# Sheet1.net
KiCad netlist of a schematic drawn in Altium Designer
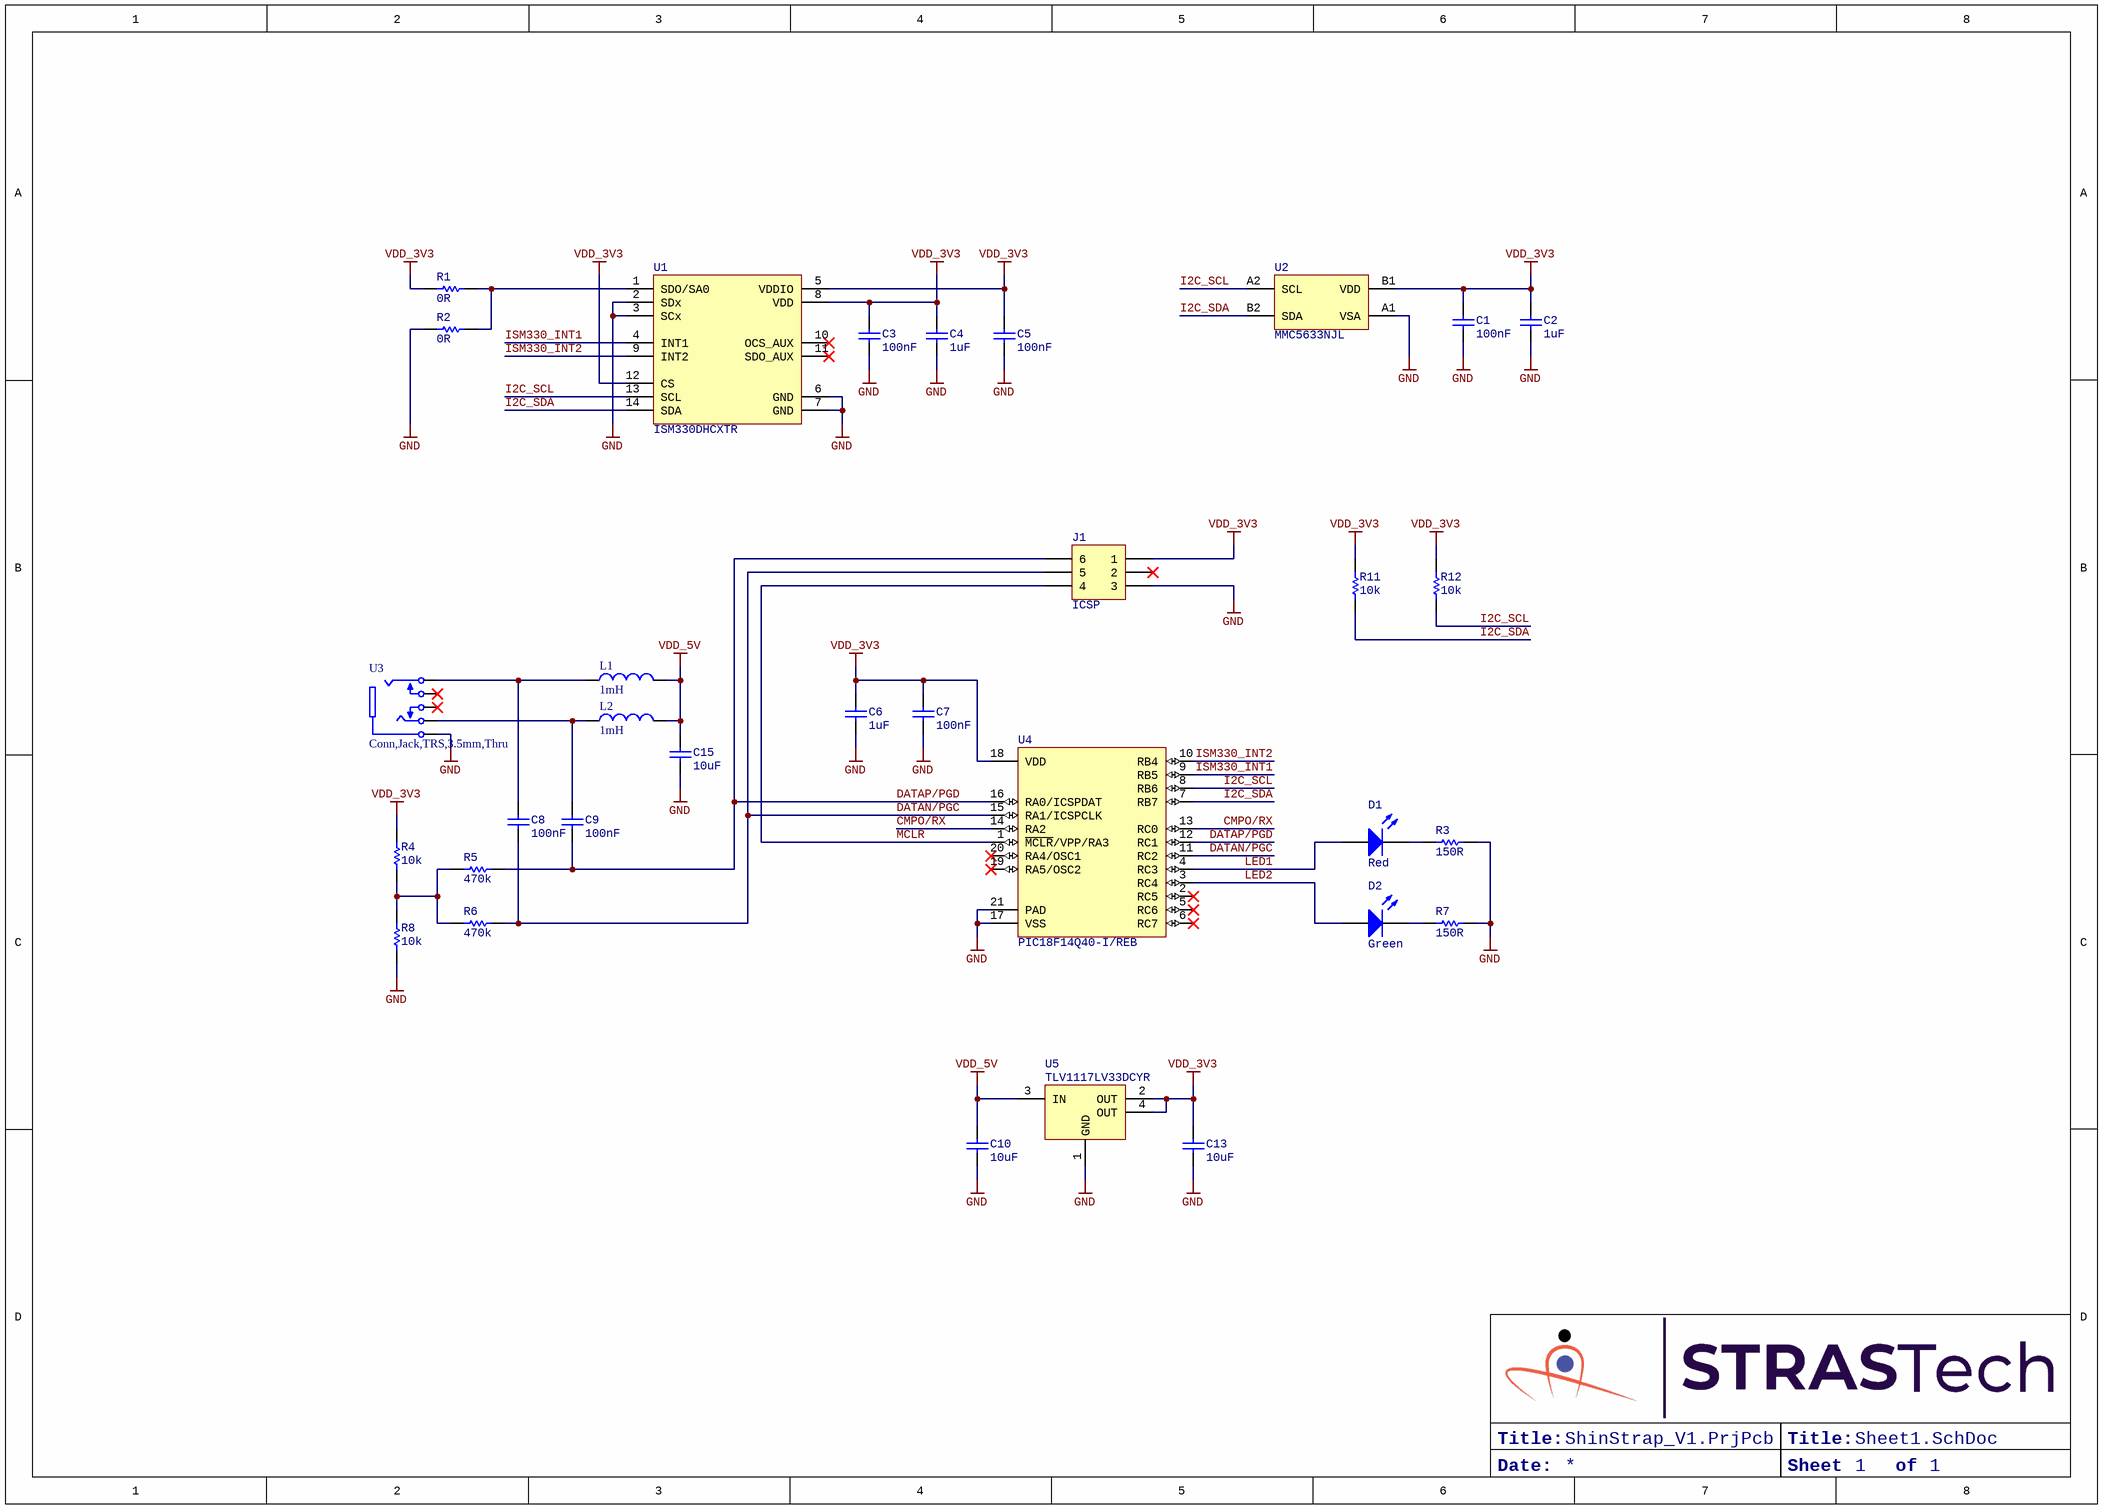
[diagram p0: Sheet1.SchDoc]

(export (version "E")
  (design (tool "Eeschema 10.0.6"))
  (components
    (comp (ref "C1")
      (value "100nF")
      (footprint "Cap,SMD,0402")
      (description "0.1µF ±10% 25V Ceramic Capacitor X7R 0402 (1005 Metric)")
      (fields
        (field (name "VENDOR PART NUMBER") "490-14603-1-ND")
        (field (name "MANUFACTURER") "Murata Electronics")
        (field (name "CREATEDBY") "Judd Foster")
      )
      (libsource (lib "symbols") (part "CAP,Cer,100nF,25VDC,X7R,0402"))
    )
    (comp (ref "C2")
      (value "1uF")
      (footprint "Cap,SMD,0402")
      (description "1 µF ±10% 35V Ceramic Capacitor X5R 0402 (1005 Metric)")
      (fields
        (field (name "VENDOR PART NUMBER") "445-9073-1-ND")
        (field (name "MANUFACTURER") "TDK Corporation")
        (field (name "CREATEDBY") "Judd Foster")
      )
      (libsource (lib "symbols") (part "CAP,Cer,1uF,35VDC,X5R,0402"))
    )
    (comp (ref "C3")
      (value "100nF")
      (footprint "Cap,SMD,0402")
      (description "0.1µF ±10% 25V Ceramic Capacitor X7R 0402 (1005 Metric)")
      (fields
        (field (name "VENDOR PART NUMBER") "490-14603-1-ND")
        (field (name "MANUFACTURER") "Murata Electronics")
        (field (name "CREATEDBY") "Judd Foster")
      )
      (libsource (lib "symbols") (part "CAP,Cer,100nF,25VDC,X7R,0402"))
    )
    (comp (ref "C4")
      (value "1uF")
      (footprint "Cap,SMD,0402")
      (description "1 µF ±10% 35V Ceramic Capacitor X5R 0402 (1005 Metric)")
      (fields
        (field (name "VENDOR PART NUMBER") "445-9073-1-ND")
        (field (name "MANUFACTURER") "TDK Corporation")
        (field (name "CREATEDBY") "Judd Foster")
      )
      (libsource (lib "symbols") (part "CAP,Cer,1uF,35VDC,X5R,0402"))
    )
    (comp (ref "C5")
      (value "100nF")
      (footprint "Cap,SMD,0402")
      (description "0.1µF ±10% 25V Ceramic Capacitor X7R 0402 (1005 Metric)")
      (fields
        (field (name "VENDOR PART NUMBER") "490-14603-1-ND")
        (field (name "MANUFACTURER") "Murata Electronics")
        (field (name "CREATEDBY") "Judd Foster")
      )
      (libsource (lib "symbols") (part "CAP,Cer,100nF,25VDC,X7R,0402"))
    )
    (comp (ref "C6")
      (value "1uF")
      (footprint "Cap,SMD,0402")
      (description "1 µF ±10% 35V Ceramic Capacitor X5R 0402 (1005 Metric)")
      (fields
        (field (name "VENDOR PART NUMBER") "445-9073-1-ND")
        (field (name "MANUFACTURER") "TDK Corporation")
        (field (name "CREATEDBY") "Judd Foster")
      )
      (libsource (lib "symbols") (part "CAP,Cer,1uF,35VDC,X5R,0402"))
    )
    (comp (ref "C7")
      (value "100nF")
      (footprint "Cap,SMD,0402")
      (description "0.1µF ±10% 25V Ceramic Capacitor X7R 0402 (1005 Metric)")
      (fields
        (field (name "VENDOR PART NUMBER") "490-14603-1-ND")
        (field (name "MANUFACTURER") "Murata Electronics")
        (field (name "CREATEDBY") "Judd Foster")
      )
      (libsource (lib "symbols") (part "CAP,Cer,100nF,25VDC,X7R,0402"))
    )
    (comp (ref "C8")
      (value "100nF")
      (footprint "Cap,SMD,0402")
      (description "0.1µF ±10% 25V Ceramic Capacitor X7R 0402 (1005 Metric)")
      (fields
        (field (name "VENDOR PART NUMBER") "490-14603-1-ND")
        (field (name "MANUFACTURER") "Murata Electronics")
        (field (name "CREATEDBY") "Judd Foster")
      )
      (libsource (lib "symbols") (part "CAP,Cer,100nF,25VDC,X7R,0402"))
    )
    (comp (ref "C9")
      (value "100nF")
      (footprint "Cap,SMD,0402")
      (description "0.1µF ±10% 25V Ceramic Capacitor X7R 0402 (1005 Metric)")
      (fields
        (field (name "VENDOR PART NUMBER") "490-14603-1-ND")
        (field (name "MANUFACTURER") "Murata Electronics")
        (field (name "CREATEDBY") "Judd Foster")
      )
      (libsource (lib "symbols") (part "CAP,Cer,100nF,25VDC,X7R,0402"))
    )
    (comp (ref "C10")
      (value "10uF")
      (footprint "Cap,SMD,0402")
      (description "10 µF ±20% 10V Ceramic Capacitor X5R 0402 (1005 Metric)")
      (fields
        (field (name "VENDOR PART NUMBER") "1276-1450-1-ND")
        (field (name "MANUFACTURER") "Samsung Electro-Mechanics")
        (field (name "CREATEDBY") "Judd Foster")
      )
      (libsource (lib "symbols") (part "CAP,Cer,10uF,10VDC,X5R,0402"))
    )
    (comp (ref "C13")
      (value "10uF")
      (footprint "Cap,SMD,0402")
      (description "10 µF ±20% 10V Ceramic Capacitor X5R 0402 (1005 Metric)")
      (fields
        (field (name "VENDOR PART NUMBER") "1276-1450-1-ND")
        (field (name "MANUFACTURER") "Samsung Electro-Mechanics")
        (field (name "CREATEDBY") "Judd Foster")
      )
      (libsource (lib "symbols") (part "CAP,Cer,10uF,10VDC,X5R,0402"))
    )
    (comp (ref "C15")
      (value "10uF")
      (footprint "Cap,SMD,0402")
      (description "10 µF ±20% 10V Ceramic Capacitor X5R 0402 (1005 Metric)")
      (fields
        (field (name "VENDOR PART NUMBER") "1276-1450-1-ND")
        (field (name "MANUFACTURER") "Samsung Electro-Mechanics")
        (field (name "CREATEDBY") "Judd Foster")
      )
      (libsource (lib "symbols") (part "CAP,Cer,10uF,10VDC,X5R,0402"))
    )
    (comp (ref "D1")
      (value "Red")
      (footprint "LED,0603")
      (description "Red 633nm LED Indication - Discrete 2V 0603 (1608 Metric)")
      (fields
        (field (name "MANUFACTURER") "Lite-On Inc.")
        (field (name "MANUFACTURER PART NUMBER") "LS Q976-NR-1")
        (field (name "CREATEDBY") "Judd Foster")
      )
      (libsource (lib "symbols") (part "LED,Red,SMD,0603"))
    )
    (comp (ref "D2")
      (value "Green")
      (footprint "LED,0603")
      (description "Green 530nm LED Indication - Discrete 3V 0603 (1608 Metric)")
      (fields
        (field (name "MANUFACTURER") "Stanley Electric Co")
        (field (name "MANUFACTURER PART NUMBER") "THG1111C-0005-TR")
        (field (name "CREATEDBY") "Judd Foster")
      )
      (libsource (lib "symbols") (part "LED,Green,SMD,0603"))
    )
    (comp (ref "J1")
      (value "Term,Header,3x2 Pin,1.27mm,SMD")
      (footprint "TERM,HEADER,3X2PIN,P1.27,SMD")
      (description "Connector Header Surface Mount 6 position 0.050\" (1.27mm)")
      (fields
        (field (name "VENDOR PART NUMBER") "609-3693-1-ND")
        (field (name "MANUFACTURER") "Amphenol ICC (FCI)")
        (field (name "CREATEDBY") "Judd Foster")
      )
      (libsource (lib "symbols") (part "Term,Header,3x2 Pin,1.27mm,SMD"))
    )
    (comp (ref "L1")
      (value "1mH")
      (footprint "IND,1210")
      (description "1 mH Unshielded Wirewound Inductor 100 mA 16.9Ohm Max 1210 (3225 Metric)")
      (fields
        (field (name "VENDOR PART NUMBER") "587-CBC3225T102MRCT-ND")
        (field (name "MANUFACTURER") "Taiyo Yuden")
        (field (name "CREATEDBY") "Judd Foster")
      )
      (libsource (lib "symbols") (part "IND,1mH,100mA,Wirewound,1210"))
    )
    (comp (ref "L2")
      (value "1mH")
      (footprint "IND,1210")
      (description "1 mH Unshielded Wirewound Inductor 100 mA 16.9Ohm Max 1210 (3225 Metric)")
      (fields
        (field (name "VENDOR PART NUMBER") "587-CBC3225T102MRCT-ND")
        (field (name "MANUFACTURER") "Taiyo Yuden")
        (field (name "CREATEDBY") "Judd Foster")
      )
      (libsource (lib "symbols") (part "IND,1mH,100mA,Wirewound,1210"))
    )
    (comp (ref "R1")
      (value "0R")
      (footprint "RES,0402")
      (description "0 Ohms Jumper 0.1W, 1/10W Chip Resistor 0402 (1005 Metric) Automotive AEC-Q200 Thick Film")
      (fields
        (field (name "MANUFACTURER") "Panasonic Electronic Components")
        (field (name "MANUFACTURER PART NUMBER") "ERJ-2GE0R00X")
        (field (name "CREATEDBY") "Judd Foster")
      )
      (libsource (lib "symbols") (part "RES,0R0,0.1W,0402"))
    )
    (comp (ref "R2")
      (value "0R")
      (footprint "RES,0402")
      (description "0 Ohms Jumper 0.1W, 1/10W Chip Resistor 0402 (1005 Metric) Automotive AEC-Q200 Thick Film")
      (fields
        (field (name "MANUFACTURER") "Panasonic Electronic Components")
        (field (name "MANUFACTURER PART NUMBER") "ERJ-2GE0R00X")
        (field (name "CREATEDBY") "Judd Foster")
      )
      (libsource (lib "symbols") (part "RES,0R0,0.1W,0402"))
    )
    (comp (ref "R3")
      (value "150R")
      (footprint "RES,0402")
      (fields
        (field (name "MANUFACTURER") "TE Connectivity Passive Product")
        (field (name "MANUFACTURER PART NUMBER") "CRGCQ0402F150R")
        (field (name "VENDOR PART NUMBER") "A129617CT-ND")
        (field (name "CREATEDBY") "Judd Foster")
      )
      (libsource (lib "symbols") (part "RES,150R,1%,0.1W,0402"))
    )
    (comp (ref "R4")
      (value "10k")
      (footprint "RES,0402")
      (description "10 kOhms ±5% 0.063W, 1/16W Chip Resistor 0402 (1005 Metric) Automotive AEC-Q200 Thick Film")
      (fields
        (field (name "VENDOR PART NUMBER") "RMCF0402JT10K0CT-ND")
        (field (name "MANUFACTURER") "Stackpole Electronics Inc")
        (field (name "CREATEDBY") "Judd Foster")
      )
      (libsource (lib "symbols") (part "RES,10k,5%,0.063W,0402"))
    )
    (comp (ref "R5")
      (value "470k")
      (footprint "RES,0402")
      (description "470 kOhms ±5% 0.063W, 1/16W Chip Resistor 0402 (1005 Metric) Automotive AEC-Q200 Thick Film")
      (fields
        (field (name "MANUFACTURER") "Stackpole Electronics Inc")
        (field (name "MANUFACTURER PART NUMBER") "RMCF0402JT470K")
        (field (name "CREATEDBY") "Judd Foster")
      )
      (libsource (lib "symbols") (part "RES,470k,5%,0.063W,0402"))
    )
    (comp (ref "R6")
      (value "470k")
      (footprint "RES,0402")
      (description "470 kOhms ±5% 0.063W, 1/16W Chip Resistor 0402 (1005 Metric) Automotive AEC-Q200 Thick Film")
      (fields
        (field (name "MANUFACTURER") "Stackpole Electronics Inc")
        (field (name "MANUFACTURER PART NUMBER") "RMCF0402JT470K")
        (field (name "CREATEDBY") "Judd Foster")
      )
      (libsource (lib "symbols") (part "RES,470k,5%,0.063W,0402"))
    )
    (comp (ref "R7")
      (value "150R")
      (footprint "RES,0402")
      (fields
        (field (name "MANUFACTURER") "TE Connectivity Passive Product")
        (field (name "MANUFACTURER PART NUMBER") "CRGCQ0402F150R")
        (field (name "VENDOR PART NUMBER") "A129617CT-ND")
        (field (name "CREATEDBY") "Judd Foster")
      )
      (libsource (lib "symbols") (part "RES,150R,1%,0.1W,0402"))
    )
    (comp (ref "R8")
      (value "10k")
      (footprint "RES,0402")
      (description "10 kOhms ±5% 0.063W, 1/16W Chip Resistor 0402 (1005 Metric) Automotive AEC-Q200 Thick Film")
      (fields
        (field (name "VENDOR PART NUMBER") "RMCF0402JT10K0CT-ND")
        (field (name "MANUFACTURER") "Stackpole Electronics Inc")
        (field (name "CREATEDBY") "Judd Foster")
      )
      (libsource (lib "symbols") (part "RES,10k,5%,0.063W,0402"))
    )
    (comp (ref "R11")
      (value "10k")
      (footprint "RES,0402")
      (description "10 kOhms ±5% 0.063W, 1/16W Chip Resistor 0402 (1005 Metric) Automotive AEC-Q200 Thick Film")
      (fields
        (field (name "VENDOR PART NUMBER") "RMCF0402JT10K0CT-ND")
        (field (name "MANUFACTURER") "Stackpole Electronics Inc")
        (field (name "CREATEDBY") "Judd Foster")
      )
      (libsource (lib "symbols") (part "RES,10k,5%,0.063W,0402"))
    )
    (comp (ref "R12")
      (value "10k")
      (footprint "RES,0402")
      (description "10 kOhms ±5% 0.063W, 1/16W Chip Resistor 0402 (1005 Metric) Automotive AEC-Q200 Thick Film")
      (fields
        (field (name "VENDOR PART NUMBER") "RMCF0402JT10K0CT-ND")
        (field (name "MANUFACTURER") "Stackpole Electronics Inc")
        (field (name "CREATEDBY") "Judd Foster")
      )
      (libsource (lib "symbols") (part "RES,10k,5%,0.063W,0402"))
    )
    (comp (ref "U1")
      (value "ISM330DHCXTR")
      (footprint "IC,LGA-14L,2.5x3mm")
      (description "Accelerometer, Gyroscope, Temperature, 6 Axis Sensor I²C, SPI Output")
      (fields
        (field (name "MANUFACTURER") "STMicroelectronics")
        (field (name "VENDOR PART NUMBER") "497-19784-1-ND")
        (field (name "CREATEDBY") "Judd Foster")
      )
      (libsource (lib "symbols") (part "ISM330DHCXTR"))
    )
    (comp (ref "U2")
      (value "MMC5633NJL")
      (footprint "IC,WLP,2x2,P0.4mm")
      (description "Magnetoresistive Sensor X, Y, Z Axis 4-WLP (0.85x0.85)")
      (fields
        (field (name "MANUFACTURER") "Memsic Inc.")
        (field (name "VENDOR PART NUMBER") "1267-MMC5633NJLCT-ND")
        (field (name "CREATEDBY") "Judd Foster")
      )
      (libsource (lib "symbols") (part "MMC5633NJL"))
    )
    (comp (ref "U3")
      (value "Conn,Jack,TRS,3.5mm,Thru")
      (footprint "CONN,JACK,TRS,3.5MM,THRU")
      (fields
        (field (name "MANUFACTURER") "CUI Devices")
        (field (name "MANUFACTURER PART NUMBER") "SJ1-3525N")
        (field (name "VENDOR PART NUMBER") "CP1-3525N-ND")
        (field (name "CREATEDBY") "Judd Foster")
      )
      (libsource (lib "symbols") (part "Conn,Jack,TRS,3.5mm,Thru"))
    )
    (comp (ref "U4")
      (value "PIC18F14Q40-I/REB")
      (footprint "IC,QFN-20,3x3,PAD,P0.4")
      (description "PIC series Microcontroller IC 8-Bit 64MHz 16KB (16K x 8) FLASH 20-VQFN (3x3)")
      (fields
        (field (name "MANUFACTURER") "Microchip Technology")
        (field (name "VENDOR PART NUMBER") "150-PIC18F14Q40-I/REB-ND")
        (field (name "CREATEDBY") "Judd Foster")
      )
      (libsource (lib "symbols") (part "PIC18F14Q40-I/REB"))
    )
    (comp (ref "U5")
      (value "TLV1117LV33DCYR")
      (footprint "SOT223")
      (description "Linear Voltage Regulator IC  1 Output  1A SOT-223-4")
      (fields
        (field (name "MANUFACTURER") "Texas Instruments")
        (field (name "VENDOR PART NUMBER") "296-28778-1-ND")
        (field (name "CREATEDBY") "Judd Foster")
      )
      (libsource (lib "symbols") (part "TLV1117LV33DCYR"))
    )
  )
  (nets
    (net (code "1") (name "/CMPO{slash}RX") (class "Default")
      (node (ref "U4") (pin "13") (pinfunction "RC0_13") (pintype "bidirectional"))
      (node (ref "U4") (pin "14") (pinfunction "RA2_14") (pintype "bidirectional"))
    )
    (net (code "2") (name "/DATAN{slash}PGC") (class "Default")
      (node (ref "C8") (pin "1") (pinfunction "1_1") (pintype "passive"))
      (node (ref "J1") (pin "5") (pinfunction "5_5") (pintype "passive"))
      (node (ref "R6") (pin "1") (pinfunction "1_1") (pintype "passive"))
      (node (ref "U4") (pin "11") (pinfunction "RC2_11") (pintype "bidirectional"))
      (node (ref "U4") (pin "15") (pinfunction "RA1/ICSPCLK_15") (pintype "bidirectional"))
    )
    (net (code "3") (name "/DATAP{slash}PGD") (class "Default")
      (node (ref "C9") (pin "1") (pinfunction "1_1") (pintype "passive"))
      (node (ref "J1") (pin "6") (pinfunction "6_6") (pintype "passive"))
      (node (ref "R5") (pin "1") (pinfunction "1_1") (pintype "passive"))
      (node (ref "U4") (pin "12") (pinfunction "RC1_12") (pintype "bidirectional"))
      (node (ref "U4") (pin "16") (pinfunction "RA0/ICSPDAT_16") (pintype "bidirectional"))
    )
    (net (code "4") (name "/I2C_SCL") (class "Default")
      (node (ref "R12") (pin "1") (pinfunction "1_1") (pintype "passive"))
      (node (ref "U1") (pin "13") (pinfunction "SCL_13") (pintype "passive"))
      (node (ref "U2") (pin "A2") (pinfunction "SCL_A2") (pintype "passive"))
      (node (ref "U4") (pin "8") (pinfunction "RB6_8") (pintype "bidirectional"))
    )
    (net (code "5") (name "/I2C_SDA") (class "Default")
      (node (ref "R11") (pin "1") (pinfunction "1_1") (pintype "passive"))
      (node (ref "U1") (pin "14") (pinfunction "SDA_14") (pintype "passive"))
      (node (ref "U2") (pin "B2") (pinfunction "SDA_B2") (pintype "passive"))
      (node (ref "U4") (pin "7") (pinfunction "RB7_7") (pintype "bidirectional"))
    )
    (net (code "6") (name "/ISM330_INT1") (class "Default")
      (node (ref "U1") (pin "4") (pinfunction "INT1_4") (pintype "passive"))
      (node (ref "U4") (pin "9") (pinfunction "RB5_9") (pintype "bidirectional"))
    )
    (net (code "7") (name "/ISM330_INT2") (class "Default")
      (node (ref "U1") (pin "9") (pinfunction "INT2_9") (pintype "passive"))
      (node (ref "U4") (pin "10") (pinfunction "RB4_10") (pintype "bidirectional"))
    )
    (net (code "8") (name "/LED1") (class "Default")
      (node (ref "D1") (pin "1") (pinfunction "A_1") (pintype "passive"))
      (node (ref "U4") (pin "4") (pinfunction "RC3_4") (pintype "bidirectional"))
    )
    (net (code "9") (name "/LED2") (class "Default")
      (node (ref "D2") (pin "1") (pinfunction "A_1") (pintype "passive"))
      (node (ref "U4") (pin "3") (pinfunction "RC4_3") (pintype "bidirectional"))
    )
    (net (code "10") (name "/~{MCLR}") (class "Default")
      (node (ref "J1") (pin "4") (pinfunction "4_4") (pintype "passive"))
      (node (ref "U4") (pin "1") (pinfunction "~{MCLR}/VPP/RA3_1") (pintype "bidirectional"))
    )
    (net (code "11") (name "GND") (class "Default")
      (node (ref "C1") (pin "2") (pinfunction "2_2") (pintype "passive"))
      (node (ref "C10") (pin "1") (pinfunction "1_1") (pintype "passive"))
      (node (ref "C13") (pin "1") (pinfunction "1_1") (pintype "passive"))
      (node (ref "C15") (pin "1") (pinfunction "1_1") (pintype "passive"))
      (node (ref "C2") (pin "1") (pinfunction "1_1") (pintype "passive"))
      (node (ref "C3") (pin "1") (pinfunction "1_1") (pintype "passive"))
      (node (ref "C4") (pin "1") (pinfunction "1_1") (pintype "passive"))
      (node (ref "C5") (pin "1") (pinfunction "1_1") (pintype "passive"))
      (node (ref "C6") (pin "1") (pinfunction "1_1") (pintype "passive"))
      (node (ref "C7") (pin "1") (pinfunction "1_1") (pintype "passive"))
      (node (ref "J1") (pin "3") (pinfunction "3_3") (pintype "passive"))
      (node (ref "R2") (pin "1") (pinfunction "1_1") (pintype "passive"))
      (node (ref "R3") (pin "2") (pinfunction "2_2") (pintype "passive"))
      (node (ref "R7") (pin "2") (pinfunction "2_2") (pintype "passive"))
      (node (ref "R8") (pin "1") (pinfunction "1_1") (pintype "passive"))
      (node (ref "U1") (pin "2") (pinfunction "SDx_2") (pintype "passive"))
      (node (ref "U1") (pin "3") (pinfunction "SCx_3") (pintype "passive"))
      (node (ref "U1") (pin "6") (pinfunction "GND_6") (pintype "passive"))
      (node (ref "U1") (pin "7") (pinfunction "GND_7") (pintype "passive"))
      (node (ref "U2") (pin "A1") (pinfunction "VSA_A1") (pintype "passive"))
      (node (ref "U3") (pin "1") (pinfunction "S_1") (pintype "power_in"))
      (node (ref "U4") (pin "17") (pinfunction "VSS_17") (pintype "power_in"))
      (node (ref "U4") (pin "21") (pinfunction "PAD_21") (pintype "passive"))
      (node (ref "U5") (pin "1") (pinfunction "GND_1") (pintype "passive"))
    )
    (net (code "12") (name "Net-(D1-K)") (class "Default")
      (node (ref "D1") (pin "2") (pinfunction "K_2") (pintype "passive"))
      (node (ref "R3") (pin "1") (pinfunction "1_1") (pintype "passive"))
    )
    (net (code "13") (name "Net-(D2-K)") (class "Default")
      (node (ref "D2") (pin "2") (pinfunction "K_2") (pintype "passive"))
      (node (ref "R7") (pin "1") (pinfunction "1_1") (pintype "passive"))
    )
    (net (code "14") (name "Net-(R4-Pad1)") (class "Default")
      (node (ref "R4") (pin "1") (pinfunction "1_1") (pintype "passive"))
      (node (ref "R5") (pin "2") (pinfunction "2_2") (pintype "passive"))
      (node (ref "R6") (pin "2") (pinfunction "2_2") (pintype "passive"))
      (node (ref "R8") (pin "2") (pinfunction "2_2") (pintype "passive"))
    )
    (net (code "15") (name "Net-(U1-SDO{slash}SA0)") (class "Default")
      (node (ref "R1") (pin "2") (pinfunction "2_2") (pintype "passive"))
      (node (ref "R2") (pin "2") (pinfunction "2_2") (pintype "passive"))
      (node (ref "U1") (pin "1") (pinfunction "SDO/SA0_1") (pintype "passive"))
    )
    (net (code "16") (name "Net-(U3-R)") (class "Default")
      (node (ref "C8") (pin "2") (pinfunction "2_2") (pintype "passive"))
      (node (ref "L1") (pin "1") (pinfunction "1_1") (pintype "passive"))
      (node (ref "U3") (pin "3") (pinfunction "R_3") (pintype "passive"))
    )
    (net (code "17") (name "Net-(U3-T)") (class "Default")
      (node (ref "C9") (pin "2") (pinfunction "2_2") (pintype "passive"))
      (node (ref "L2") (pin "1") (pinfunction "1_1") (pintype "passive"))
      (node (ref "U3") (pin "2") (pinfunction "T_2") (pintype "passive"))
    )
    (net (code "18") (name "VDD_3V3") (class "Default")
      (node (ref "C1") (pin "1") (pinfunction "1_1") (pintype "passive"))
      (node (ref "C13") (pin "2") (pinfunction "2_2") (pintype "passive"))
      (node (ref "C2") (pin "2") (pinfunction "2_2") (pintype "passive"))
      (node (ref "C3") (pin "2") (pinfunction "2_2") (pintype "passive"))
      (node (ref "C4") (pin "2") (pinfunction "2_2") (pintype "passive"))
      (node (ref "C5") (pin "2") (pinfunction "2_2") (pintype "passive"))
      (node (ref "C6") (pin "2") (pinfunction "2_2") (pintype "passive"))
      (node (ref "C7") (pin "2") (pinfunction "2_2") (pintype "passive"))
      (node (ref "J1") (pin "1") (pinfunction "1_1") (pintype "passive"))
      (node (ref "R1") (pin "1") (pinfunction "1_1") (pintype "passive"))
      (node (ref "R11") (pin "2") (pinfunction "2_2") (pintype "passive"))
      (node (ref "R12") (pin "2") (pinfunction "2_2") (pintype "passive"))
      (node (ref "R4") (pin "2") (pinfunction "2_2") (pintype "passive"))
      (node (ref "U1") (pin "12") (pinfunction "CS_12") (pintype "passive"))
      (node (ref "U1") (pin "5") (pinfunction "VDDIO_5") (pintype "passive"))
      (node (ref "U1") (pin "8") (pinfunction "VDD_8") (pintype "passive"))
      (node (ref "U2") (pin "B1") (pinfunction "VDD_B1") (pintype "passive"))
      (node (ref "U4") (pin "18") (pinfunction "VDD_18") (pintype "power_in"))
      (node (ref "U5") (pin "2") (pinfunction "OUT_2") (pintype "passive"))
      (node (ref "U5") (pin "4") (pinfunction "OUT_4") (pintype "passive"))
    )
    (net (code "19") (name "VDD_5V") (class "Default")
      (node (ref "C10") (pin "2") (pinfunction "2_2") (pintype "passive"))
      (node (ref "C15") (pin "2") (pinfunction "2_2") (pintype "passive"))
      (node (ref "L1") (pin "2") (pinfunction "2_2") (pintype "passive"))
      (node (ref "L2") (pin "2") (pinfunction "2_2") (pintype "passive"))
      (node (ref "U5") (pin "3") (pinfunction "IN_3") (pintype "passive"))
    )
    (net (code "20") (name "unconnected-(J1-Pad2)") (class "Default")
      (node (ref "J1") (pin "2") (pinfunction "2_2") (pintype "passive+no_connect"))
    )
    (net (code "21") (name "unconnected-(U1-OCS_AUX-Pad10)") (class "Default")
      (node (ref "U1") (pin "10") (pinfunction "OCS_AUX_10") (pintype "passive+no_connect"))
    )
    (net (code "22") (name "unconnected-(U1-SDO_AUX-Pad11)") (class "Default")
      (node (ref "U1") (pin "11") (pinfunction "SDO_AUX_11") (pintype "passive+no_connect"))
    )
    (net (code "23") (name "unconnected-(U3-RS-Pad11)") (class "Default")
      (node (ref "U3") (pin "11") (pinfunction "RS_11") (pintype "passive+no_connect"))
    )
    (net (code "24") (name "unconnected-(U3-TS-Pad10)") (class "Default")
      (node (ref "U3") (pin "10") (pinfunction "TS_10") (pintype "passive+no_connect"))
    )
    (net (code "25") (name "unconnected-(U4-RA4{slash}OSC1-Pad20)") (class "Default")
      (node (ref "U4") (pin "20") (pinfunction "RA4/OSC1_20") (pintype "bidirectional+no_connect"))
    )
    (net (code "26") (name "unconnected-(U4-RA5{slash}OSC2-Pad19)") (class "Default")
      (node (ref "U4") (pin "19") (pinfunction "RA5/OSC2_19") (pintype "bidirectional+no_connect"))
    )
    (net (code "27") (name "unconnected-(U4-RC5-Pad2)") (class "Default")
      (node (ref "U4") (pin "2") (pinfunction "RC5_2") (pintype "bidirectional+no_connect"))
    )
    (net (code "28") (name "unconnected-(U4-RC6-Pad5)") (class "Default")
      (node (ref "U4") (pin "5") (pinfunction "RC6_5") (pintype "bidirectional+no_connect"))
    )
    (net (code "29") (name "unconnected-(U4-RC7-Pad6)") (class "Default")
      (node (ref "U4") (pin "6") (pinfunction "RC7_6") (pintype "bidirectional+no_connect"))
    )
  )
)
